# rfid_v3.net
KiCad netlist of a schematic drawn in EAGLE
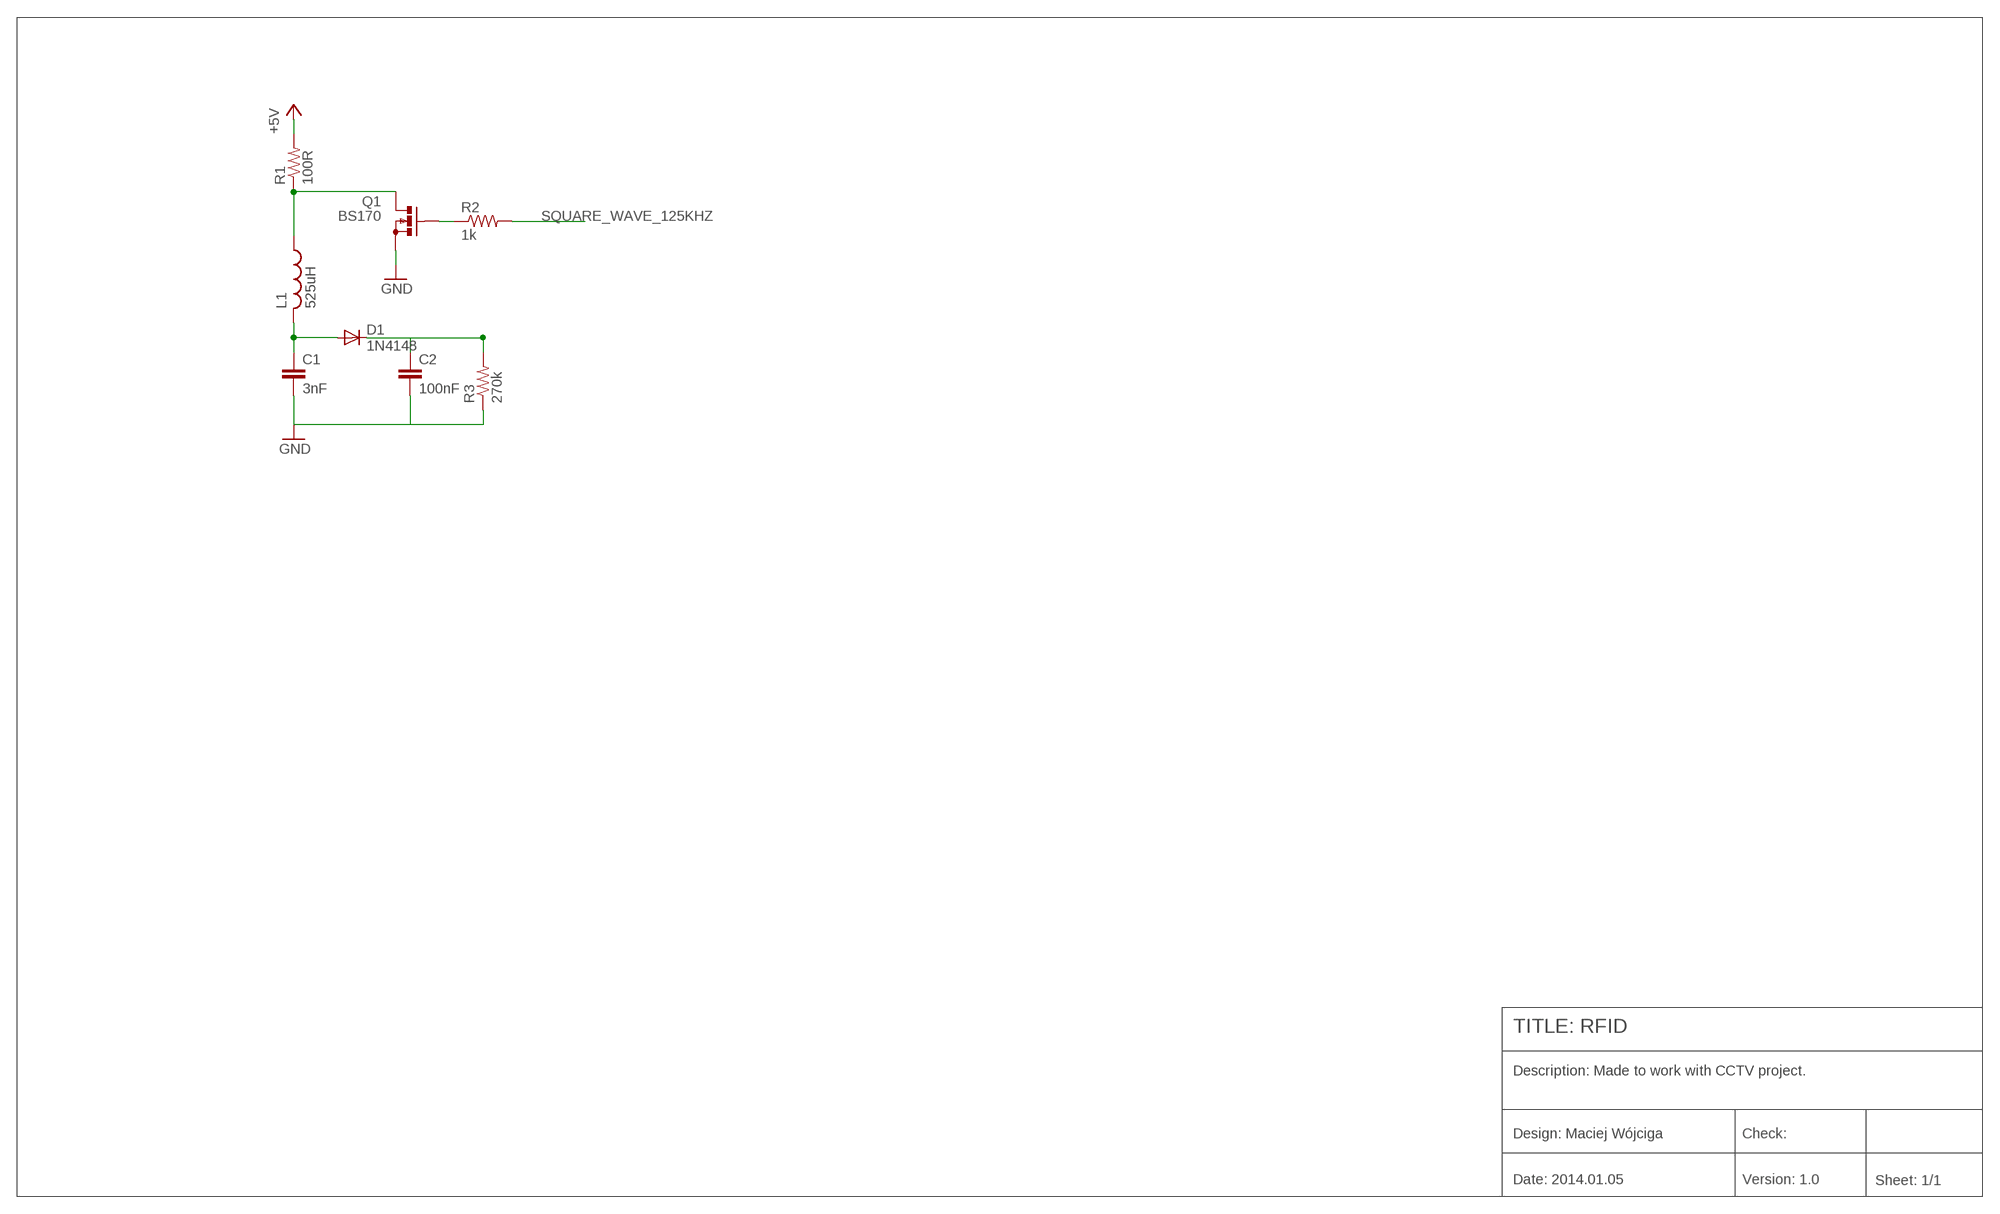
[diagram p0: schematic, sheet 1]

(export (version "E")
  (design (tool "Eeschema 10.0.6"))
  (components
    (comp (ref "C1")
      (value "3nF")
      (footprint "eagle-import:C025-050X050")
      (libsource (lib "eagle-import") (part "C-EU025-050X050"))
    )
    (comp (ref "C2")
      (value "100nF")
      (footprint "eagle-import:C025-050X050")
      (libsource (lib "eagle-import") (part "C-EU025-050X050"))
    )
    (comp (ref "D1")
      (value "1N4148")
      (footprint "eagle-import:DO35-7")
      (libsource (lib "eagle-import") (part "1N4148DO35-7"))
    )
    (comp (ref "L1")
      (value "525uH")
      (footprint "eagle-import:0204_5")
      (libsource (lib "eagle-import") (part "L-US0204/5"))
    )
    (comp (ref "Q1")
      (value "BS170")
      (footprint "eagle-import:SOT54E")
      (libsource (lib "eagle-import") (part "BS170"))
    )
    (comp (ref "R1")
      (value "100R")
      (footprint "eagle-import:0309_10")
      (libsource (lib "eagle-import") (part "R-US_0309/10"))
    )
    (comp (ref "R2")
      (value "1k")
      (footprint "eagle-import:0309_10")
      (libsource (lib "eagle-import") (part "R-US_0309/10"))
    )
    (comp (ref "R3")
      (value "270k")
      (footprint "eagle-import:0309_10")
      (libsource (lib "eagle-import") (part "R-US_0309/10"))
    )
  )
  (nets
    (net (code "1") (name "+5V") (class "Default")
      (node (ref "R1") (pin "2") (pinfunction "2_2") (pintype "passive"))
    )
    (net (code "2") (name "/SQUARE_WAVE_125KHZ") (class "Default")
      (node (ref "R2") (pin "2") (pinfunction "2_2") (pintype "passive"))
    )
    (net (code "3") (name "GND") (class "Default")
      (node (ref "C1") (pin "2") (pinfunction "2_2") (pintype "passive"))
      (node (ref "C2") (pin "2") (pinfunction "2_2") (pintype "passive"))
      (node (ref "Q1") (pin "S") (pinfunction "S_S") (pintype "passive"))
      (node (ref "R3") (pin "1") (pinfunction "1_1") (pintype "passive"))
    )
    (net (code "4") (name "Net-(C1-Pad1)") (class "Default")
      (node (ref "C1") (pin "1") (pinfunction "1_1") (pintype "passive"))
      (node (ref "D1") (pin "A") (pinfunction "A_A") (pintype "passive"))
      (node (ref "L1") (pin "2") (pinfunction "2_2") (pintype "passive"))
    )
    (net (code "5") (name "Net-(C2-Pad1)") (class "Default")
      (node (ref "C2") (pin "1") (pinfunction "1_1") (pintype "passive"))
      (node (ref "D1") (pin "C") (pinfunction "C_C") (pintype "passive"))
      (node (ref "R3") (pin "2") (pinfunction "2_2") (pintype "passive"))
    )
    (net (code "6") (name "Net-(L1-Pad1)") (class "Default")
      (node (ref "L1") (pin "1") (pinfunction "1_1") (pintype "passive"))
      (node (ref "Q1") (pin "D") (pinfunction "D_D") (pintype "passive"))
      (node (ref "R1") (pin "1") (pinfunction "1_1") (pintype "passive"))
    )
    (net (code "7") (name "Net-(Q1-PadG)") (class "Default")
      (node (ref "Q1") (pin "G") (pinfunction "G_G") (pintype "passive"))
      (node (ref "R2") (pin "1") (pinfunction "1_1") (pintype "passive"))
    )
  )
)
